# a12008mb.net
KiCad netlist of a schematic drawn in EAGLE
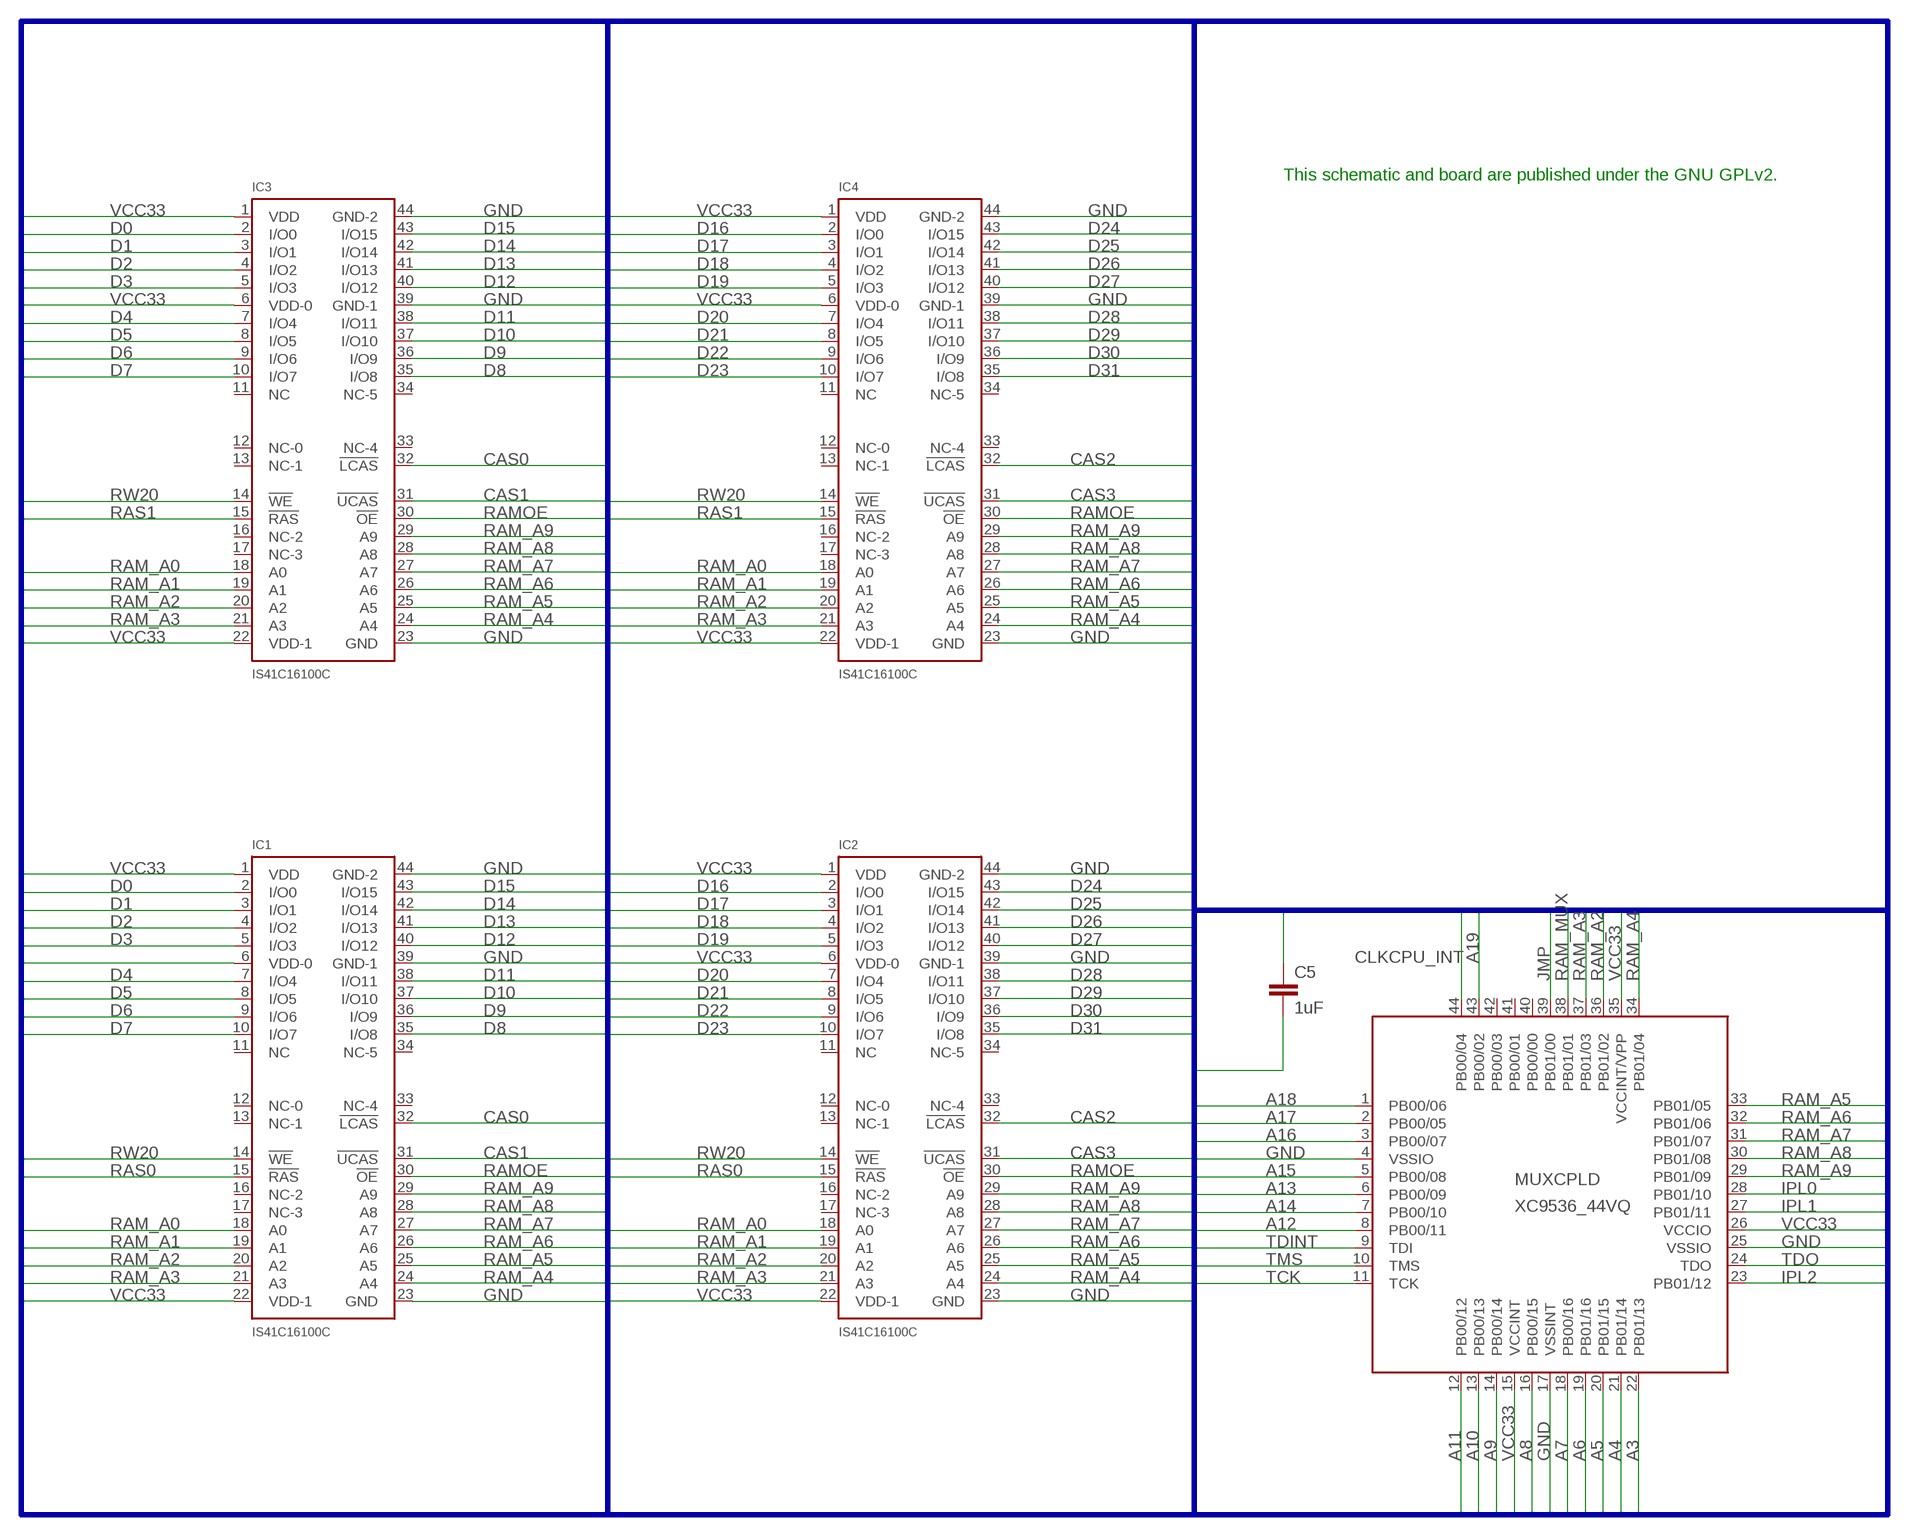
[diagram p0: schematic, sheet 1]
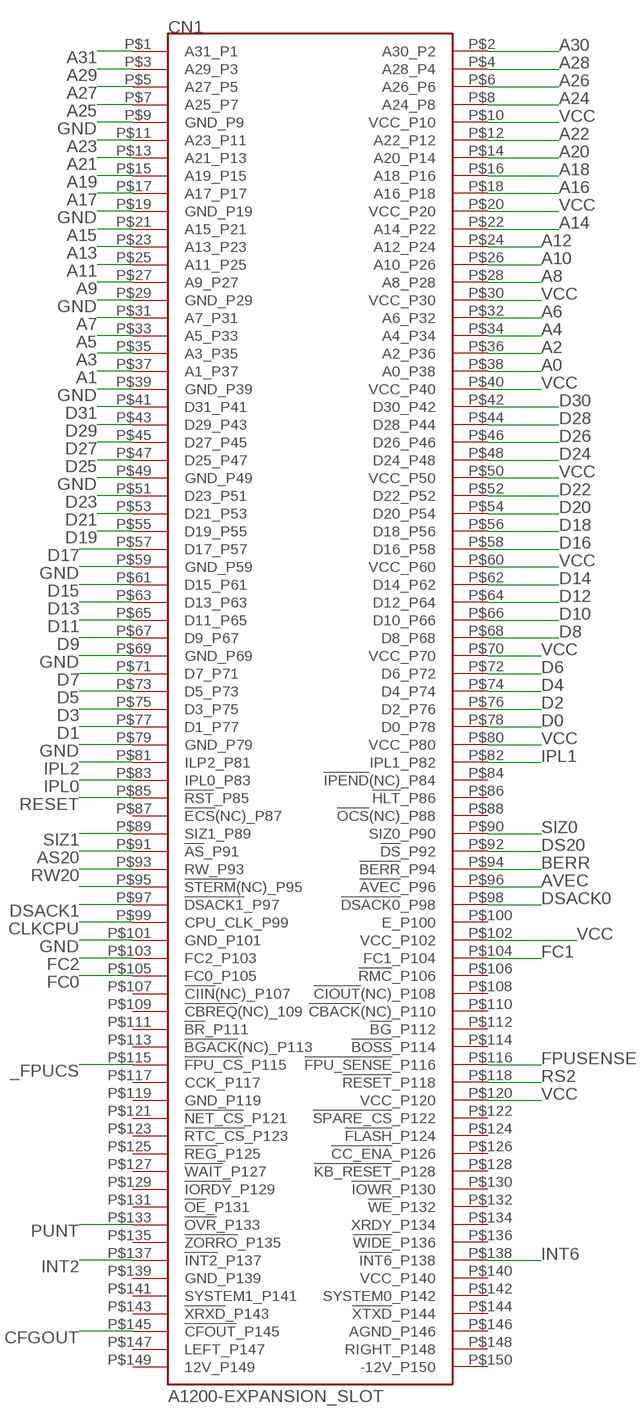
[diagram p1: schematic, sheet 2]
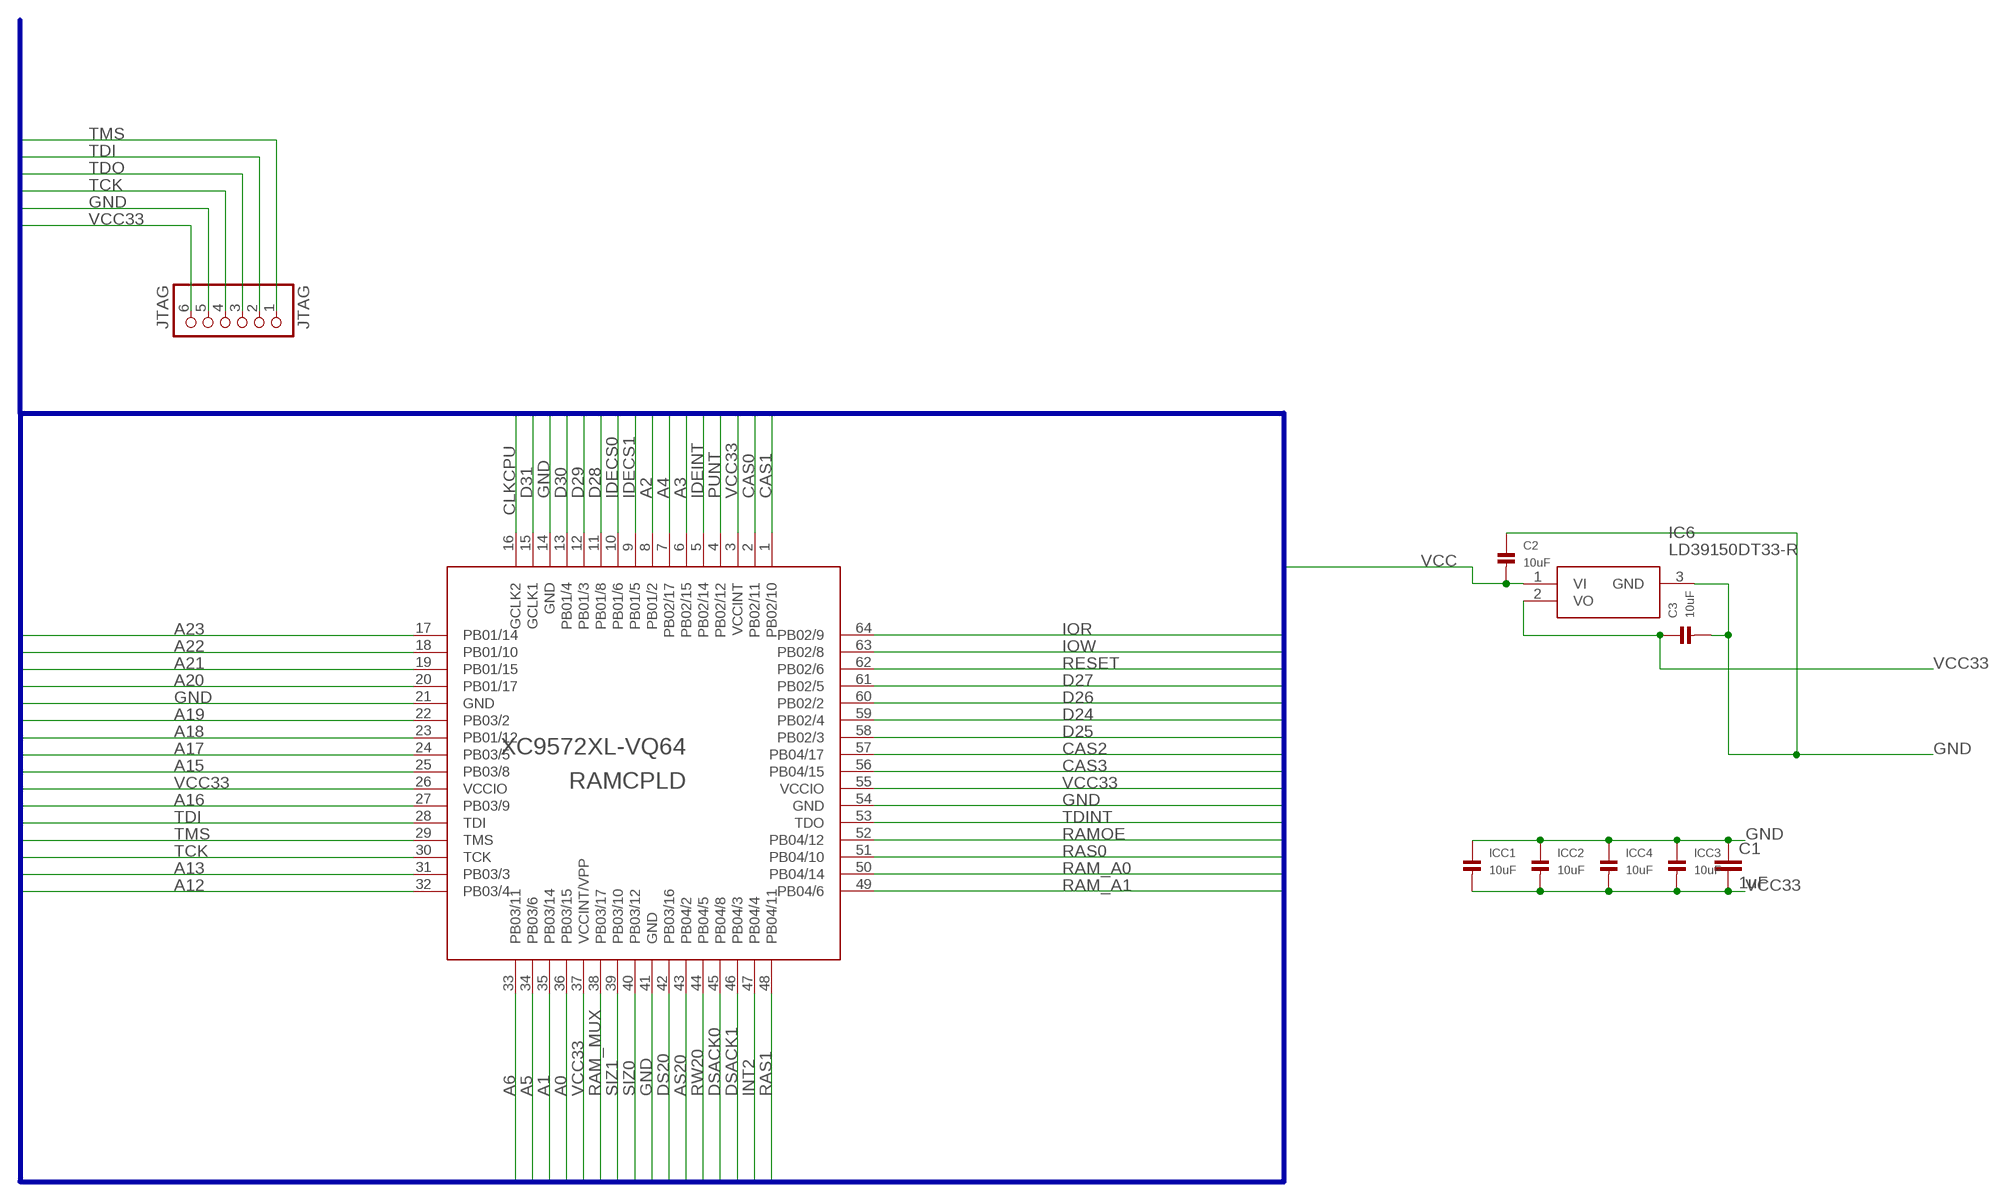
[diagram p2: schematic, sheet 3]

(export (version "E")
  (design (tool "Eeschema 10.0.6"))
  (components
    (comp (ref "C5")
      (value "1uF")
      (footprint "eagle-import:C1206")
      (libsource (lib "eagle-import") (part "CC1206"))
    )
    (comp (ref "IC1")
      (value "IS41C16100C")
      (footprint "eagle-import:TSOP44(50)-II")
      (libsource (lib "eagle-import") (part "IS41C16100C"))
    )
    (comp (ref "IC2")
      (value "IS41C16100C")
      (footprint "eagle-import:TSOP44(50)-II")
      (libsource (lib "eagle-import") (part "IS41C16100C"))
    )
    (comp (ref "IC3")
      (value "IS41C16100C")
      (footprint "eagle-import:TSOP44(50)-II")
      (libsource (lib "eagle-import") (part "IS41C16100C"))
    )
    (comp (ref "IC4")
      (value "IS41C16100C")
      (footprint "eagle-import:TSOP44(50)-II")
      (libsource (lib "eagle-import") (part "IS41C16100C"))
    )
    (comp (ref "MUXCPLD")
      (value "XC9536_44VQ")
      (footprint "eagle-import:SQFP-S-10X10-44")
      (fields (field (name "MPN") "XC9536-15VQG44C"))
      (libsource (lib "eagle-import") (part "XC9536_44VQ"))
    )
    (comp (ref "CN1")
      (value "A1200-EXPANSION_SLOT")
      (footprint "eagle-import:CON_150")
      (libsource (lib "eagle-import") (part "A1200-EXPANSION_SLOT"))
    )
    (comp (ref "C1")
      (value "1uF")
      (footprint "eagle-import:C1206")
      (libsource (lib "eagle-import") (part "CC1206"))
    )
    (comp (ref "C2")
      (value "10uF")
      (footprint "eagle-import:1206")
      (libsource (lib "eagle-import") (part "CAP_CERAMIC1206"))
    )
    (comp (ref "C3")
      (value "10uF")
      (footprint "eagle-import:1206")
      (libsource (lib "eagle-import") (part "CAP_CERAMIC1206"))
    )
    (comp (ref "IC6")
      (value "LD39150DT33-R")
      (footprint "eagle-import:STD5N52U")
      (fields (field (name "MOUSER_PART_NUMBER") "511-LD39150DT33-R"))
      (libsource (lib "eagle-import") (part "LD39150DT33-R"))
    )
    (comp (ref "ICC1")
      (value "10uF")
      (footprint "eagle-import:1206")
      (libsource (lib "eagle-import") (part "CAP_CERAMIC1206"))
    )
    (comp (ref "ICC2")
      (value "10uF")
      (footprint "eagle-import:1206")
      (libsource (lib "eagle-import") (part "CAP_CERAMIC1206"))
    )
    (comp (ref "ICC3")
      (value "10uF")
      (footprint "eagle-import:1206")
      (libsource (lib "eagle-import") (part "CAP_CERAMIC1206"))
    )
    (comp (ref "ICC4")
      (value "10uF")
      (footprint "eagle-import:1206")
      (libsource (lib "eagle-import") (part "CAP_CERAMIC1206"))
    )
    (comp (ref "JTAG")
      (value "JTAG")
      (footprint "eagle-import:1X06_ROUND")
      (libsource (lib "eagle-import") (part "HEADER-1X6ROUND"))
    )
    (comp (ref "RAMCPLD")
      (value "XC9572XL-VQ64")
      (footprint "eagle-import:VQ64")
      (libsource (lib "eagle-import") (part "XC9572XL-VQ64"))
    )
  )
  (nets
    (net (code "1") (name "A0") (class "Default")
      (node (ref "CN1") (pin "P$38") (pinfunction "A0_P38_P$38") (pintype "bidirectional"))
      (node (ref "RAMCPLD") (pin "36") (pinfunction "PB03/15_36") (pintype "bidirectional"))
    )
    (net (code "2") (name "A1") (class "Default")
      (node (ref "CN1") (pin "P$37") (pinfunction "A1_P37_P$37") (pintype "bidirectional"))
      (node (ref "RAMCPLD") (pin "35") (pinfunction "PB03/14_35") (pintype "bidirectional"))
    )
    (net (code "3") (name "A2") (class "Default")
      (node (ref "CN1") (pin "P$36") (pinfunction "A2_P36_P$36") (pintype "bidirectional"))
      (node (ref "RAMCPLD") (pin "8") (pinfunction "PB01/2_8") (pintype "bidirectional"))
    )
    (net (code "4") (name "A3") (class "Default")
      (node (ref "CN1") (pin "P$35") (pinfunction "A3_P35_P$35") (pintype "bidirectional"))
      (node (ref "MUXCPLD") (pin "22") (pinfunction "PB01/13_22") (pintype "bidirectional"))
      (node (ref "RAMCPLD") (pin "6") (pinfunction "PB02/15_6") (pintype "bidirectional"))
    )
    (net (code "5") (name "A4") (class "Default")
      (node (ref "CN1") (pin "P$34") (pinfunction "A4_P34_P$34") (pintype "bidirectional"))
      (node (ref "MUXCPLD") (pin "21") (pinfunction "PB01/14_21") (pintype "bidirectional"))
      (node (ref "RAMCPLD") (pin "7") (pinfunction "PB02/17_7") (pintype "bidirectional"))
    )
    (net (code "6") (name "A5") (class "Default")
      (node (ref "CN1") (pin "P$33") (pinfunction "A5_P33_P$33") (pintype "bidirectional"))
      (node (ref "MUXCPLD") (pin "20") (pinfunction "PB01/15_20") (pintype "bidirectional"))
      (node (ref "RAMCPLD") (pin "34") (pinfunction "PB03/6_34") (pintype "bidirectional"))
    )
    (net (code "7") (name "A6") (class "Default")
      (node (ref "CN1") (pin "P$32") (pinfunction "A6_P32_P$32") (pintype "bidirectional"))
      (node (ref "MUXCPLD") (pin "19") (pinfunction "PB01/16_19") (pintype "bidirectional"))
      (node (ref "RAMCPLD") (pin "33") (pinfunction "PB03/11_33") (pintype "bidirectional"))
    )
    (net (code "8") (name "A7") (class "Default")
      (node (ref "CN1") (pin "P$31") (pinfunction "A7_P31_P$31") (pintype "bidirectional"))
      (node (ref "MUXCPLD") (pin "18") (pinfunction "PB00/16_18") (pintype "bidirectional"))
    )
    (net (code "9") (name "A8") (class "Default")
      (node (ref "CN1") (pin "P$28") (pinfunction "A8_P28_P$28") (pintype "bidirectional"))
      (node (ref "MUXCPLD") (pin "16") (pinfunction "PB00/15_16") (pintype "bidirectional"))
    )
    (net (code "10") (name "A9") (class "Default")
      (node (ref "CN1") (pin "P$27") (pinfunction "A9_P27_P$27") (pintype "bidirectional"))
      (node (ref "MUXCPLD") (pin "14") (pinfunction "PB00/14_14") (pintype "bidirectional"))
    )
    (net (code "11") (name "A10") (class "Default")
      (node (ref "CN1") (pin "P$26") (pinfunction "A10_P26_P$26") (pintype "bidirectional"))
      (node (ref "MUXCPLD") (pin "13") (pinfunction "PB00/13_13") (pintype "bidirectional"))
    )
    (net (code "12") (name "A11") (class "Default")
      (node (ref "CN1") (pin "P$25") (pinfunction "A11_P25_P$25") (pintype "bidirectional"))
      (node (ref "MUXCPLD") (pin "12") (pinfunction "PB00/12_12") (pintype "bidirectional"))
    )
    (net (code "13") (name "A12") (class "Default")
      (node (ref "CN1") (pin "P$24") (pinfunction "A12_P24_P$24") (pintype "bidirectional"))
      (node (ref "MUXCPLD") (pin "8") (pinfunction "PB00/11_8") (pintype "bidirectional"))
      (node (ref "RAMCPLD") (pin "32") (pinfunction "PB03/4_32") (pintype "bidirectional"))
    )
    (net (code "14") (name "A13") (class "Default")
      (node (ref "CN1") (pin "P$23") (pinfunction "A13_P23_P$23") (pintype "bidirectional"))
      (node (ref "MUXCPLD") (pin "6") (pinfunction "PB00/09_6") (pintype "bidirectional"))
      (node (ref "RAMCPLD") (pin "31") (pinfunction "PB03/3_31") (pintype "bidirectional"))
    )
    (net (code "15") (name "A14") (class "Default")
      (node (ref "CN1") (pin "P$22") (pinfunction "A14_P22_P$22") (pintype "bidirectional"))
      (node (ref "MUXCPLD") (pin "7") (pinfunction "PB00/10_7") (pintype "bidirectional"))
    )
    (net (code "16") (name "A15") (class "Default")
      (node (ref "CN1") (pin "P$21") (pinfunction "A15_P21_P$21") (pintype "bidirectional"))
      (node (ref "MUXCPLD") (pin "5") (pinfunction "PB00/08_5") (pintype "bidirectional"))
      (node (ref "RAMCPLD") (pin "25") (pinfunction "PB03/8_25") (pintype "bidirectional"))
    )
    (net (code "17") (name "A16") (class "Default")
      (node (ref "CN1") (pin "P$18") (pinfunction "A16_P18_P$18") (pintype "bidirectional"))
      (node (ref "MUXCPLD") (pin "3") (pinfunction "PB00/07_3") (pintype "bidirectional"))
      (node (ref "RAMCPLD") (pin "27") (pinfunction "PB03/9_27") (pintype "bidirectional"))
    )
    (net (code "18") (name "A17") (class "Default")
      (node (ref "CN1") (pin "P$17") (pinfunction "A17_P17_P$17") (pintype "bidirectional"))
      (node (ref "MUXCPLD") (pin "2") (pinfunction "PB00/05_2") (pintype "bidirectional"))
      (node (ref "RAMCPLD") (pin "24") (pinfunction "PB03/5_24") (pintype "bidirectional"))
    )
    (net (code "19") (name "A18") (class "Default")
      (node (ref "CN1") (pin "P$16") (pinfunction "A18_P16_P$16") (pintype "bidirectional"))
      (node (ref "MUXCPLD") (pin "1") (pinfunction "PB00/06_1") (pintype "bidirectional"))
      (node (ref "RAMCPLD") (pin "23") (pinfunction "PB01/12_23") (pintype "bidirectional"))
    )
    (net (code "20") (name "A19") (class "Default")
      (node (ref "CN1") (pin "P$15") (pinfunction "A19_P15_P$15") (pintype "bidirectional"))
      (node (ref "MUXCPLD") (pin "43") (pinfunction "PB00/02_43") (pintype "bidirectional"))
      (node (ref "RAMCPLD") (pin "22") (pinfunction "PB03/2_22") (pintype "bidirectional"))
    )
    (net (code "21") (name "A20") (class "Default")
      (node (ref "CN1") (pin "P$14") (pinfunction "A20_P14_P$14") (pintype "bidirectional"))
      (node (ref "RAMCPLD") (pin "20") (pinfunction "PB01/17_20") (pintype "bidirectional"))
    )
    (net (code "22") (name "A21") (class "Default")
      (node (ref "CN1") (pin "P$13") (pinfunction "A21_P13_P$13") (pintype "bidirectional"))
      (node (ref "RAMCPLD") (pin "19") (pinfunction "PB01/15_19") (pintype "bidirectional"))
    )
    (net (code "23") (name "A22") (class "Default")
      (node (ref "CN1") (pin "P$12") (pinfunction "A22_P12_P$12") (pintype "bidirectional"))
      (node (ref "RAMCPLD") (pin "18") (pinfunction "PB01/10_18") (pintype "bidirectional"))
    )
    (net (code "24") (name "A23") (class "Default")
      (node (ref "CN1") (pin "P$11") (pinfunction "A23_P11_P$11") (pintype "bidirectional"))
      (node (ref "RAMCPLD") (pin "17") (pinfunction "PB01/14_17") (pintype "bidirectional"))
    )
    (net (code "25") (name "A24") (class "Default")
      (node (ref "CN1") (pin "P$8") (pinfunction "A24_P8_P$8") (pintype "bidirectional"))
    )
    (net (code "26") (name "A25") (class "Default")
      (node (ref "CN1") (pin "P$7") (pinfunction "A25_P7_P$7") (pintype "bidirectional"))
    )
    (net (code "27") (name "A26") (class "Default")
      (node (ref "CN1") (pin "P$6") (pinfunction "A26_P6_P$6") (pintype "bidirectional"))
    )
    (net (code "28") (name "A27") (class "Default")
      (node (ref "CN1") (pin "P$5") (pinfunction "A27_P5_P$5") (pintype "bidirectional"))
    )
    (net (code "29") (name "A28") (class "Default")
      (node (ref "CN1") (pin "P$4") (pinfunction "A28_P4_P$4") (pintype "bidirectional"))
    )
    (net (code "30") (name "A29") (class "Default")
      (node (ref "CN1") (pin "P$3") (pinfunction "A29_P3_P$3") (pintype "bidirectional"))
    )
    (net (code "31") (name "A30") (class "Default")
      (node (ref "CN1") (pin "P$2") (pinfunction "A30_P2_P$2") (pintype "bidirectional"))
    )
    (net (code "32") (name "A31") (class "Default")
      (node (ref "CN1") (pin "P$1") (pinfunction "A31_P1_P$1") (pintype "bidirectional"))
    )
    (net (code "33") (name "AS20") (class "Default")
      (node (ref "CN1") (pin "P$91") (pinfunction "~{AS}_P91_P$91") (pintype "bidirectional"))
      (node (ref "RAMCPLD") (pin "43") (pinfunction "PB04/2_43") (pintype "bidirectional"))
    )
    (net (code "34") (name "AVEC") (class "Default")
      (node (ref "CN1") (pin "P$96") (pinfunction "~{AVEC}_P96_P$96") (pintype "bidirectional"))
    )
    (net (code "35") (name "BERR") (class "Default")
      (node (ref "CN1") (pin "P$94") (pinfunction "~{BERR}_P94_P$94") (pintype "bidirectional"))
    )
    (net (code "36") (name "CAS0") (class "Default")
      (node (ref "IC1") (pin "32") (pinfunction "~{LCAS}_32") (pintype "bidirectional"))
      (node (ref "IC3") (pin "32") (pinfunction "~{LCAS}_32") (pintype "bidirectional"))
      (node (ref "RAMCPLD") (pin "2") (pinfunction "PB02/11_2") (pintype "bidirectional"))
    )
    (net (code "37") (name "CAS1") (class "Default")
      (node (ref "IC1") (pin "31") (pinfunction "~{UCAS}_31") (pintype "bidirectional"))
      (node (ref "IC3") (pin "31") (pinfunction "~{UCAS}_31") (pintype "bidirectional"))
      (node (ref "RAMCPLD") (pin "1") (pinfunction "PB02/10_1") (pintype "bidirectional"))
    )
    (net (code "38") (name "CAS2") (class "Default")
      (node (ref "IC2") (pin "32") (pinfunction "~{LCAS}_32") (pintype "bidirectional"))
      (node (ref "IC4") (pin "32") (pinfunction "~{LCAS}_32") (pintype "bidirectional"))
      (node (ref "RAMCPLD") (pin "57") (pinfunction "PB04/17_57") (pintype "bidirectional"))
    )
    (net (code "39") (name "CAS3") (class "Default")
      (node (ref "IC2") (pin "31") (pinfunction "~{UCAS}_31") (pintype "bidirectional"))
      (node (ref "IC4") (pin "31") (pinfunction "~{UCAS}_31") (pintype "bidirectional"))
      (node (ref "RAMCPLD") (pin "56") (pinfunction "PB04/15_56") (pintype "bidirectional"))
    )
    (net (code "40") (name "CFGOUT") (class "Default")
      (node (ref "CN1") (pin "P$145") (pinfunction "~{CFOUT}_P145_P$145") (pintype "bidirectional"))
    )
    (net (code "41") (name "CLKCPU") (class "Default")
      (node (ref "CN1") (pin "P$99") (pinfunction "CPU_CLK_P99_P$99") (pintype "bidirectional"))
      (node (ref "RAMCPLD") (pin "16") (pinfunction "GCLK2_16") (pintype "bidirectional"))
    )
    (net (code "42") (name "CLKCPU_INT") (class "Default")
      (node (ref "MUXCPLD") (pin "44") (pinfunction "PB00/04_44") (pintype "bidirectional"))
    )
    (net (code "43") (name "D0") (class "Default")
      (node (ref "CN1") (pin "P$78") (pinfunction "D0_P78_P$78") (pintype "bidirectional"))
      (node (ref "IC1") (pin "2") (pinfunction "I/O0_2") (pintype "bidirectional"))
      (node (ref "IC3") (pin "2") (pinfunction "I/O0_2") (pintype "bidirectional"))
    )
    (net (code "44") (name "D1") (class "Default")
      (node (ref "CN1") (pin "P$77") (pinfunction "D1_P77_P$77") (pintype "bidirectional"))
      (node (ref "IC1") (pin "3") (pinfunction "I/O1_3") (pintype "bidirectional"))
      (node (ref "IC3") (pin "3") (pinfunction "I/O1_3") (pintype "bidirectional"))
    )
    (net (code "45") (name "D2") (class "Default")
      (node (ref "CN1") (pin "P$76") (pinfunction "D2_P76_P$76") (pintype "bidirectional"))
      (node (ref "IC1") (pin "4") (pinfunction "I/O2_4") (pintype "bidirectional"))
      (node (ref "IC3") (pin "4") (pinfunction "I/O2_4") (pintype "bidirectional"))
    )
    (net (code "46") (name "D3") (class "Default")
      (node (ref "CN1") (pin "P$75") (pinfunction "D3_P75_P$75") (pintype "bidirectional"))
      (node (ref "IC1") (pin "5") (pinfunction "I/O3_5") (pintype "bidirectional"))
      (node (ref "IC3") (pin "5") (pinfunction "I/O3_5") (pintype "bidirectional"))
    )
    (net (code "47") (name "D4") (class "Default")
      (node (ref "CN1") (pin "P$74") (pinfunction "D4_P74_P$74") (pintype "bidirectional"))
      (node (ref "IC1") (pin "7") (pinfunction "I/O4_7") (pintype "bidirectional"))
      (node (ref "IC3") (pin "7") (pinfunction "I/O4_7") (pintype "bidirectional"))
    )
    (net (code "48") (name "D5") (class "Default")
      (node (ref "CN1") (pin "P$73") (pinfunction "D5_P73_P$73") (pintype "bidirectional"))
      (node (ref "IC1") (pin "8") (pinfunction "I/O5_8") (pintype "bidirectional"))
      (node (ref "IC3") (pin "8") (pinfunction "I/O5_8") (pintype "bidirectional"))
    )
    (net (code "49") (name "D6") (class "Default")
      (node (ref "CN1") (pin "P$72") (pinfunction "D6_P72_P$72") (pintype "bidirectional"))
      (node (ref "IC1") (pin "9") (pinfunction "I/O6_9") (pintype "bidirectional"))
      (node (ref "IC3") (pin "9") (pinfunction "I/O6_9") (pintype "bidirectional"))
    )
    (net (code "50") (name "D7") (class "Default")
      (node (ref "CN1") (pin "P$71") (pinfunction "D7_P71_P$71") (pintype "bidirectional"))
      (node (ref "IC1") (pin "10") (pinfunction "I/O7_10") (pintype "bidirectional"))
      (node (ref "IC3") (pin "10") (pinfunction "I/O7_10") (pintype "bidirectional"))
    )
    (net (code "51") (name "D8") (class "Default")
      (node (ref "CN1") (pin "P$68") (pinfunction "D8_P68_P$68") (pintype "bidirectional"))
      (node (ref "IC1") (pin "35") (pinfunction "I/O8_35") (pintype "bidirectional"))
      (node (ref "IC3") (pin "35") (pinfunction "I/O8_35") (pintype "bidirectional"))
    )
    (net (code "52") (name "D9") (class "Default")
      (node (ref "CN1") (pin "P$67") (pinfunction "D9_P67_P$67") (pintype "bidirectional"))
      (node (ref "IC1") (pin "36") (pinfunction "I/O9_36") (pintype "bidirectional"))
      (node (ref "IC3") (pin "36") (pinfunction "I/O9_36") (pintype "bidirectional"))
    )
    (net (code "53") (name "D10") (class "Default")
      (node (ref "CN1") (pin "P$66") (pinfunction "D10_P66_P$66") (pintype "bidirectional"))
      (node (ref "IC1") (pin "37") (pinfunction "I/O10_37") (pintype "bidirectional"))
      (node (ref "IC3") (pin "37") (pinfunction "I/O10_37") (pintype "bidirectional"))
    )
    (net (code "54") (name "D11") (class "Default")
      (node (ref "CN1") (pin "P$65") (pinfunction "D11_P65_P$65") (pintype "bidirectional"))
      (node (ref "IC1") (pin "38") (pinfunction "I/O11_38") (pintype "bidirectional"))
      (node (ref "IC3") (pin "38") (pinfunction "I/O11_38") (pintype "bidirectional"))
    )
    (net (code "55") (name "D12") (class "Default")
      (node (ref "CN1") (pin "P$64") (pinfunction "D12_P64_P$64") (pintype "bidirectional"))
      (node (ref "IC1") (pin "40") (pinfunction "I/O12_40") (pintype "bidirectional"))
      (node (ref "IC3") (pin "40") (pinfunction "I/O12_40") (pintype "bidirectional"))
    )
    (net (code "56") (name "D13") (class "Default")
      (node (ref "CN1") (pin "P$63") (pinfunction "D13_P63_P$63") (pintype "bidirectional"))
      (node (ref "IC1") (pin "41") (pinfunction "I/O13_41") (pintype "bidirectional"))
      (node (ref "IC3") (pin "41") (pinfunction "I/O13_41") (pintype "bidirectional"))
    )
    (net (code "57") (name "D14") (class "Default")
      (node (ref "CN1") (pin "P$62") (pinfunction "D14_P62_P$62") (pintype "bidirectional"))
      (node (ref "IC1") (pin "42") (pinfunction "I/O14_42") (pintype "bidirectional"))
      (node (ref "IC3") (pin "42") (pinfunction "I/O14_42") (pintype "bidirectional"))
    )
    (net (code "58") (name "D15") (class "Default")
      (node (ref "CN1") (pin "P$61") (pinfunction "D15_P61_P$61") (pintype "bidirectional"))
      (node (ref "IC1") (pin "43") (pinfunction "I/O15_43") (pintype "bidirectional"))
      (node (ref "IC3") (pin "43") (pinfunction "I/O15_43") (pintype "bidirectional"))
    )
    (net (code "59") (name "D16") (class "Default")
      (node (ref "CN1") (pin "P$58") (pinfunction "D16_P58_P$58") (pintype "bidirectional"))
      (node (ref "IC2") (pin "2") (pinfunction "I/O0_2") (pintype "bidirectional"))
      (node (ref "IC4") (pin "2") (pinfunction "I/O0_2") (pintype "bidirectional"))
    )
    (net (code "60") (name "D17") (class "Default")
      (node (ref "CN1") (pin "P$57") (pinfunction "D17_P57_P$57") (pintype "bidirectional"))
      (node (ref "IC2") (pin "3") (pinfunction "I/O1_3") (pintype "bidirectional"))
      (node (ref "IC4") (pin "3") (pinfunction "I/O1_3") (pintype "bidirectional"))
    )
    (net (code "61") (name "D18") (class "Default")
      (node (ref "CN1") (pin "P$56") (pinfunction "D18_P56_P$56") (pintype "bidirectional"))
      (node (ref "IC2") (pin "4") (pinfunction "I/O2_4") (pintype "bidirectional"))
      (node (ref "IC4") (pin "4") (pinfunction "I/O2_4") (pintype "bidirectional"))
    )
    (net (code "62") (name "D19") (class "Default")
      (node (ref "CN1") (pin "P$55") (pinfunction "D19_P55_P$55") (pintype "bidirectional"))
      (node (ref "IC2") (pin "5") (pinfunction "I/O3_5") (pintype "bidirectional"))
      (node (ref "IC4") (pin "5") (pinfunction "I/O3_5") (pintype "bidirectional"))
    )
    (net (code "63") (name "D20") (class "Default")
      (node (ref "CN1") (pin "P$54") (pinfunction "D20_P54_P$54") (pintype "bidirectional"))
      (node (ref "IC2") (pin "7") (pinfunction "I/O4_7") (pintype "bidirectional"))
      (node (ref "IC4") (pin "7") (pinfunction "I/O4_7") (pintype "bidirectional"))
    )
    (net (code "64") (name "D21") (class "Default")
      (node (ref "CN1") (pin "P$53") (pinfunction "D21_P53_P$53") (pintype "bidirectional"))
      (node (ref "IC2") (pin "8") (pinfunction "I/O5_8") (pintype "bidirectional"))
      (node (ref "IC4") (pin "8") (pinfunction "I/O5_8") (pintype "bidirectional"))
    )
    (net (code "65") (name "D22") (class "Default")
      (node (ref "CN1") (pin "P$52") (pinfunction "D22_P52_P$52") (pintype "bidirectional"))
      (node (ref "IC2") (pin "9") (pinfunction "I/O6_9") (pintype "bidirectional"))
      (node (ref "IC4") (pin "9") (pinfunction "I/O6_9") (pintype "bidirectional"))
    )
    (net (code "66") (name "D23") (class "Default")
      (node (ref "CN1") (pin "P$51") (pinfunction "D23_P51_P$51") (pintype "bidirectional"))
      (node (ref "IC2") (pin "10") (pinfunction "I/O7_10") (pintype "bidirectional"))
      (node (ref "IC4") (pin "10") (pinfunction "I/O7_10") (pintype "bidirectional"))
    )
    (net (code "67") (name "D24") (class "Default")
      (node (ref "CN1") (pin "P$48") (pinfunction "D24_P48_P$48") (pintype "bidirectional"))
      (node (ref "IC2") (pin "43") (pinfunction "I/O15_43") (pintype "bidirectional"))
      (node (ref "IC4") (pin "43") (pinfunction "I/O15_43") (pintype "bidirectional"))
      (node (ref "RAMCPLD") (pin "59") (pinfunction "PB02/4_59") (pintype "bidirectional"))
    )
    (net (code "68") (name "D25") (class "Default")
      (node (ref "CN1") (pin "P$47") (pinfunction "D25_P47_P$47") (pintype "bidirectional"))
      (node (ref "IC2") (pin "42") (pinfunction "I/O14_42") (pintype "bidirectional"))
      (node (ref "IC4") (pin "42") (pinfunction "I/O14_42") (pintype "bidirectional"))
      (node (ref "RAMCPLD") (pin "58") (pinfunction "PB02/3_58") (pintype "bidirectional"))
    )
    (net (code "69") (name "D26") (class "Default")
      (node (ref "CN1") (pin "P$46") (pinfunction "D26_P46_P$46") (pintype "bidirectional"))
      (node (ref "IC2") (pin "41") (pinfunction "I/O13_41") (pintype "bidirectional"))
      (node (ref "IC4") (pin "41") (pinfunction "I/O13_41") (pintype "bidirectional"))
      (node (ref "RAMCPLD") (pin "60") (pinfunction "PB02/2_60") (pintype "bidirectional"))
    )
    (net (code "70") (name "D27") (class "Default")
      (node (ref "CN1") (pin "P$45") (pinfunction "D27_P45_P$45") (pintype "bidirectional"))
      (node (ref "IC2") (pin "40") (pinfunction "I/O12_40") (pintype "bidirectional"))
      (node (ref "IC4") (pin "40") (pinfunction "I/O12_40") (pintype "bidirectional"))
      (node (ref "RAMCPLD") (pin "61") (pinfunction "PB02/5_61") (pintype "bidirectional"))
    )
    (net (code "71") (name "D28") (class "Default")
      (node (ref "CN1") (pin "P$44") (pinfunction "D28_P44_P$44") (pintype "bidirectional"))
      (node (ref "IC2") (pin "38") (pinfunction "I/O11_38") (pintype "bidirectional"))
      (node (ref "IC4") (pin "38") (pinfunction "I/O11_38") (pintype "bidirectional"))
      (node (ref "RAMCPLD") (pin "11") (pinfunction "PB01/8_11") (pintype "bidirectional"))
    )
    (net (code "72") (name "D29") (class "Default")
      (node (ref "CN1") (pin "P$43") (pinfunction "D29_P43_P$43") (pintype "bidirectional"))
      (node (ref "IC2") (pin "37") (pinfunction "I/O10_37") (pintype "bidirectional"))
      (node (ref "IC4") (pin "37") (pinfunction "I/O10_37") (pintype "bidirectional"))
      (node (ref "RAMCPLD") (pin "12") (pinfunction "PB01/3_12") (pintype "bidirectional"))
    )
    (net (code "73") (name "D30") (class "Default")
      (node (ref "CN1") (pin "P$42") (pinfunction "D30_P42_P$42") (pintype "bidirectional"))
      (node (ref "IC2") (pin "36") (pinfunction "I/O9_36") (pintype "bidirectional"))
      (node (ref "IC4") (pin "36") (pinfunction "I/O9_36") (pintype "bidirectional"))
      (node (ref "RAMCPLD") (pin "13") (pinfunction "PB01/4_13") (pintype "bidirectional"))
    )
    (net (code "74") (name "D31") (class "Default")
      (node (ref "CN1") (pin "P$41") (pinfunction "D31_P41_P$41") (pintype "bidirectional"))
      (node (ref "IC2") (pin "35") (pinfunction "I/O8_35") (pintype "bidirectional"))
      (node (ref "IC4") (pin "35") (pinfunction "I/O8_35") (pintype "bidirectional"))
      (node (ref "RAMCPLD") (pin "15") (pinfunction "GCLK1_15") (pintype "bidirectional"))
    )
    (net (code "75") (name "DS20") (class "Default")
      (node (ref "CN1") (pin "P$92") (pinfunction "~{DS}_P92_P$92") (pintype "bidirectional"))
      (node (ref "RAMCPLD") (pin "42") (pinfunction "PB03/16_42") (pintype "bidirectional"))
    )
    (net (code "76") (name "DSACK0") (class "Default")
      (node (ref "CN1") (pin "P$98") (pinfunction "~{DSACK0}_P98_P$98") (pintype "bidirectional"))
      (node (ref "RAMCPLD") (pin "45") (pinfunction "PB04/8_45") (pintype "bidirectional"))
    )
    (net (code "77") (name "DSACK1") (class "Default")
      (node (ref "CN1") (pin "P$97") (pinfunction "~{DSACK1}_P97_P$97") (pintype "bidirectional"))
      (node (ref "RAMCPLD") (pin "46") (pinfunction "PB04/3_46") (pintype "bidirectional"))
    )
    (net (code "78") (name "FC0") (class "Default")
      (node (ref "CN1") (pin "P$105") (pinfunction "FC0_P105_P$105") (pintype "bidirectional"))
    )
    (net (code "79") (name "FC1") (class "Default")
      (node (ref "CN1") (pin "P$104") (pinfunction "FC1_P104_P$104") (pintype "bidirectional"))
    )
    (net (code "80") (name "FC2") (class "Default")
      (node (ref "CN1") (pin "P$103") (pinfunction "FC2_P103_P$103") (pintype "bidirectional"))
    )
    (net (code "81") (name "FPUSENSE") (class "Default")
      (node (ref "CN1") (pin "P$116") (pinfunction "~{FPU_SENSE}_P116_P$116") (pintype "bidirectional"))
    )
    (net (code "82") (name "GND") (class "Default")
      (node (ref "C1") (pin "1") (pinfunction "1_1") (pintype "passive"))
      (node (ref "C2") (pin "1") (pinfunction "P$1_1") (pintype "passive"))
      (node (ref "C3") (pin "2") (pinfunction "P$2_2") (pintype "passive"))
      (node (ref "C5") (pin "2") (pinfunction "2_2") (pintype "passive"))
      (node (ref "CN1") (pin "P$101") (pinfunction "GND_P101_P$101") (pintype "bidirectional"))
      (node (ref "CN1") (pin "P$19") (pinfunction "GND_P19_P$19") (pintype "bidirectional"))
      (node (ref "CN1") (pin "P$29") (pinfunction "GND_P29_P$29") (pintype "bidirectional"))
      (node (ref "CN1") (pin "P$39") (pinfunction "GND_P39_P$39") (pintype "bidirectional"))
      (node (ref "CN1") (pin "P$49") (pinfunction "GND_P49_P$49") (pintype "bidirectional"))
      (node (ref "CN1") (pin "P$59") (pinfunction "GND_P59_P$59") (pintype "bidirectional"))
      (node (ref "CN1") (pin "P$69") (pinfunction "GND_P69_P$69") (pintype "bidirectional"))
      (node (ref "CN1") (pin "P$79") (pinfunction "GND_P79_P$79") (pintype "bidirectional"))
      (node (ref "CN1") (pin "P$9") (pinfunction "GND_P9_P$9") (pintype "bidirectional"))
      (node (ref "IC1") (pin "23") (pinfunction "GND_23") (pintype "bidirectional"))
      (node (ref "IC1") (pin "39") (pinfunction "GND-1_39") (pintype "bidirectional"))
      (node (ref "IC1") (pin "44") (pinfunction "GND-2_44") (pintype "bidirectional"))
      (node (ref "IC2") (pin "23") (pinfunction "GND_23") (pintype "bidirectional"))
      (node (ref "IC2") (pin "39") (pinfunction "GND-1_39") (pintype "bidirectional"))
      (node (ref "IC2") (pin "44") (pinfunction "GND-2_44") (pintype "bidirectional"))
      (node (ref "IC3") (pin "23") (pinfunction "GND_23") (pintype "bidirectional"))
      (node (ref "IC3") (pin "39") (pinfunction "GND-1_39") (pintype "bidirectional"))
      (node (ref "IC3") (pin "44") (pinfunction "GND-2_44") (pintype "bidirectional"))
      (node (ref "IC4") (pin "23") (pinfunction "GND_23") (pintype "bidirectional"))
      (node (ref "IC4") (pin "39") (pinfunction "GND-1_39") (pintype "bidirectional"))
      (node (ref "IC4") (pin "44") (pinfunction "GND-2_44") (pintype "bidirectional"))
      (node (ref "IC6") (pin "3") (pinfunction "GND_3") (pintype "bidirectional"))
      (node (ref "ICC1") (pin "1") (pinfunction "P$1_1") (pintype "passive"))
      (node (ref "ICC2") (pin "1") (pinfunction "P$1_1") (pintype "passive"))
      (node (ref "ICC3") (pin "1") (pinfunction "P$1_1") (pintype "passive"))
      (node (ref "ICC4") (pin "1") (pinfunction "P$1_1") (pintype "passive"))
      (node (ref "JTAG") (pin "5") (pinfunction "5_5") (pintype "passive"))
      (node (ref "MUXCPLD") (pin "17") (pinfunction "VSSINT_17") (pintype "power_in"))
      (node (ref "MUXCPLD") (pin "25") (pinfunction "VSSIO_25") (pintype "power_in"))
      (node (ref "MUXCPLD") (pin "4") (pinfunction "VSSIO_4") (pintype "power_in"))
      (node (ref "RAMCPLD") (pin "14") (pinfunction "GND_14") (pintype "bidirectional"))
      (node (ref "RAMCPLD") (pin "21") (pinfunction "GND_21") (pintype "bidirectional"))
      (node (ref "RAMCPLD") (pin "41") (pinfunction "GND_41") (pintype "bidirectional"))
      (node (ref "RAMCPLD") (pin "54") (pinfunction "GND_54") (pintype "bidirectional"))
    )
    (net (code "83") (name "IDECS0") (class "Default")
      (node (ref "RAMCPLD") (pin "10") (pinfunction "PB01/6_10") (pintype "bidirectional"))
    )
    (net (code "84") (name "IDECS1") (class "Default")
      (node (ref "RAMCPLD") (pin "9") (pinfunction "PB01/5_9") (pintype "bidirectional"))
    )
    (net (code "85") (name "IDEINT") (class "Default")
      (node (ref "RAMCPLD") (pin "5") (pinfunction "PB02/14_5") (pintype "bidirectional"))
    )
    (net (code "86") (name "INT2") (class "Default")
      (node (ref "CN1") (pin "P$137") (pinfunction "~{INT2}_P137_P$137") (pintype "bidirectional"))
      (node (ref "RAMCPLD") (pin "47") (pinfunction "PB04/4_47") (pintype "bidirectional"))
    )
    (net (code "87") (name "INT6") (class "Default")
      (node (ref "CN1") (pin "P$138") (pinfunction "~{INT6}_P138_P$138") (pintype "bidirectional"))
    )
    (net (code "88") (name "IOR") (class "Default")
      (node (ref "RAMCPLD") (pin "64") (pinfunction "PB02/9_64") (pintype "bidirectional"))
    )
    (net (code "89") (name "IOW") (class "Default")
      (node (ref "RAMCPLD") (pin "63") (pinfunction "PB02/8_63") (pintype "bidirectional"))
    )
    (net (code "90") (name "IPL0") (class "Default")
      (node (ref "CN1") (pin "P$83") (pinfunction "IPL0_P83_P$83") (pintype "bidirectional"))
      (node (ref "MUXCPLD") (pin "28") (pinfunction "PB01/10_28") (pintype "bidirectional"))
    )
    (net (code "91") (name "IPL1") (class "Default")
      (node (ref "CN1") (pin "P$82") (pinfunction "IPL1_P82_P$82") (pintype "bidirectional"))
      (node (ref "MUXCPLD") (pin "27") (pinfunction "PB01/11_27") (pintype "bidirectional"))
    )
    (net (code "92") (name "IPL2") (class "Default")
      (node (ref "CN1") (pin "P$81") (pinfunction "ILP2_P81_P$81") (pintype "bidirectional"))
      (node (ref "MUXCPLD") (pin "23") (pinfunction "PB01/12_23") (pintype "bidirectional"))
    )
    (net (code "93") (name "JMP") (class "Default")
      (node (ref "MUXCPLD") (pin "39") (pinfunction "PB01/00_39") (pintype "bidirectional"))
    )
    (net (code "94") (name "PUNT") (class "Default")
      (node (ref "CN1") (pin "P$133") (pinfunction "~{OVR}_P133_P$133") (pintype "bidirectional"))
      (node (ref "RAMCPLD") (pin "4") (pinfunction "PB02/12_4") (pintype "bidirectional"))
    )
    (net (code "95") (name "RAMOE") (class "Default")
      (node (ref "IC1") (pin "30") (pinfunction "~{OE}_30") (pintype "bidirectional"))
      (node (ref "IC2") (pin "30") (pinfunction "~{OE}_30") (pintype "bidirectional"))
      (node (ref "IC3") (pin "30") (pinfunction "~{OE}_30") (pintype "bidirectional"))
      (node (ref "IC4") (pin "30") (pinfunction "~{OE}_30") (pintype "bidirectional"))
      (node (ref "RAMCPLD") (pin "52") (pinfunction "PB04/12_52") (pintype "bidirectional"))
    )
    (net (code "96") (name "RAM_A0") (class "Default")
      (node (ref "IC1") (pin "18") (pinfunction "A0_18") (pintype "bidirectional"))
      (node (ref "IC2") (pin "18") (pinfunction "A0_18") (pintype "bidirectional"))
      (node (ref "IC3") (pin "18") (pinfunction "A0_18") (pintype "bidirectional"))
      (node (ref "IC4") (pin "18") (pinfunction "A0_18") (pintype "bidirectional"))
      (node (ref "RAMCPLD") (pin "50") (pinfunction "PB04/14_50") (pintype "bidirectional"))
    )
    (net (code "97") (name "RAM_A1") (class "Default")
      (node (ref "IC1") (pin "19") (pinfunction "A1_19") (pintype "bidirectional"))
      (node (ref "IC2") (pin "19") (pinfunction "A1_19") (pintype "bidirectional"))
      (node (ref "IC3") (pin "19") (pinfunction "A1_19") (pintype "bidirectional"))
      (node (ref "IC4") (pin "19") (pinfunction "A1_19") (pintype "bidirectional"))
      (node (ref "RAMCPLD") (pin "49") (pinfunction "PB04/6_49") (pintype "bidirectional"))
    )
    (net (code "98") (name "RAM_A2") (class "Default")
      (node (ref "IC1") (pin "20") (pinfunction "A2_20") (pintype "bidirectional"))
      (node (ref "IC2") (pin "20") (pinfunction "A2_20") (pintype "bidirectional"))
      (node (ref "IC3") (pin "20") (pinfunction "A2_20") (pintype "bidirectional"))
      (node (ref "IC4") (pin "20") (pinfunction "A2_20") (pintype "bidirectional"))
      (node (ref "MUXCPLD") (pin "36") (pinfunction "PB01/02_36") (pintype "bidirectional"))
    )
    (net (code "99") (name "RAM_A3") (class "Default")
      (node (ref "IC1") (pin "21") (pinfunction "A3_21") (pintype "bidirectional"))
      (node (ref "IC2") (pin "21") (pinfunction "A3_21") (pintype "bidirectional"))
      (node (ref "IC3") (pin "21") (pinfunction "A3_21") (pintype "bidirectional"))
      (node (ref "IC4") (pin "21") (pinfunction "A3_21") (pintype "bidirectional"))
      (node (ref "MUXCPLD") (pin "37") (pinfunction "PB01/03_37") (pintype "bidirectional"))
    )
    (net (code "100") (name "RAM_A4") (class "Default")
      (node (ref "IC1") (pin "24") (pinfunction "A4_24") (pintype "bidirectional"))
      (node (ref "IC2") (pin "24") (pinfunction "A4_24") (pintype "bidirectional"))
      (node (ref "IC3") (pin "24") (pinfunction "A4_24") (pintype "bidirectional"))
      (node (ref "IC4") (pin "24") (pinfunction "A4_24") (pintype "bidirectional"))
      (node (ref "MUXCPLD") (pin "34") (pinfunction "PB01/04_34") (pintype "bidirectional"))
    )
    (net (code "101") (name "RAM_A5") (class "Default")
      (node (ref "IC1") (pin "25") (pinfunction "A5_25") (pintype "bidirectional"))
      (node (ref "IC2") (pin "25") (pinfunction "A5_25") (pintype "bidirectional"))
      (node (ref "IC3") (pin "25") (pinfunction "A5_25") (pintype "bidirectional"))
      (node (ref "IC4") (pin "25") (pinfunction "A5_25") (pintype "bidirectional"))
      (node (ref "MUXCPLD") (pin "33") (pinfunction "PB01/05_33") (pintype "bidirectional"))
    )
    (net (code "102") (name "RAM_A6") (class "Default")
      (node (ref "IC1") (pin "26") (pinfunction "A6_26") (pintype "bidirectional"))
      (node (ref "IC2") (pin "26") (pinfunction "A6_26") (pintype "bidirectional"))
      (node (ref "IC3") (pin "26") (pinfunction "A6_26") (pintype "bidirectional"))
      (node (ref "IC4") (pin "26") (pinfunction "A6_26") (pintype "bidirectional"))
      (node (ref "MUXCPLD") (pin "32") (pinfunction "PB01/06_32") (pintype "bidirectional"))
    )
    (net (code "103") (name "RAM_A7") (class "Default")
      (node (ref "IC1") (pin "27") (pinfunction "A7_27") (pintype "bidirectional"))
      (node (ref "IC2") (pin "27") (pinfunction "A7_27") (pintype "bidirectional"))
      (node (ref "IC3") (pin "27") (pinfunction "A7_27") (pintype "bidirectional"))
      (node (ref "IC4") (pin "27") (pinfunction "A7_27") (pintype "bidirectional"))
      (node (ref "MUXCPLD") (pin "31") (pinfunction "PB01/07_31") (pintype "bidirectional"))
    )
    (net (code "104") (name "RAM_A8") (class "Default")
      (node (ref "IC1") (pin "28") (pinfunction "A8_28") (pintype "bidirectional"))
      (node (ref "IC2") (pin "28") (pinfunction "A8_28") (pintype "bidirectional"))
      (node (ref "IC3") (pin "28") (pinfunction "A8_28") (pintype "bidirectional"))
      (node (ref "IC4") (pin "28") (pinfunction "A8_28") (pintype "bidirectional"))
      (node (ref "MUXCPLD") (pin "30") (pinfunction "PB01/08_30") (pintype "bidirectional"))
    )
    (net (code "105") (name "RAM_A9") (class "Default")
      (node (ref "IC1") (pin "29") (pinfunction "A9_29") (pintype "bidirectional"))
      (node (ref "IC2") (pin "29") (pinfunction "A9_29") (pintype "bidirectional"))
      (node (ref "IC3") (pin "29") (pinfunction "A9_29") (pintype "bidirectional"))
      (node (ref "IC4") (pin "29") (pinfunction "A9_29") (pintype "bidirectional"))
      (node (ref "MUXCPLD") (pin "29") (pinfunction "PB01/09_29") (pintype "bidirectional"))
    )
    (net (code "106") (name "RAM_MUX") (class "Default")
      (node (ref "MUXCPLD") (pin "38") (pinfunction "PB01/01_38") (pintype "bidirectional"))
      (node (ref "RAMCPLD") (pin "38") (pinfunction "PB03/17_38") (pintype "bidirectional"))
    )
    (net (code "107") (name "RAS0") (class "Default")
      (node (ref "IC1") (pin "15") (pinfunction "~{RAS}_15") (pintype "bidirectional"))
      (node (ref "IC2") (pin "15") (pinfunction "~{RAS}_15") (pintype "bidirectional"))
      (node (ref "RAMCPLD") (pin "51") (pinfunction "PB04/10_51") (pintype "bidirectional"))
    )
    (net (code "108") (name "RAS1") (class "Default")
      (node (ref "IC3") (pin "15") (pinfunction "~{RAS}_15") (pintype "bidirectional"))
      (node (ref "IC4") (pin "15") (pinfunction "~{RAS}_15") (pintype "bidirectional"))
      (node (ref "RAMCPLD") (pin "48") (pinfunction "PB04/11_48") (pintype "bidirectional"))
    )
    (net (code "109") (name "RESET") (class "Default")
      (node (ref "CN1") (pin "P$85") (pinfunction "~{RST}_P85_P$85") (pintype "bidirectional"))
      (node (ref "RAMCPLD") (pin "62") (pinfunction "PB02/6_62") (pintype "bidirectional"))
    )
    (net (code "110") (name "RS2") (class "Default")
      (node (ref "CN1") (pin "P$118") (pinfunction "~{RESET}_P118_P$118") (pintype "bidirectional"))
    )
    (net (code "111") (name "RW20") (class "Default")
      (node (ref "CN1") (pin "P$93") (pinfunction "RW_P93_P$93") (pintype "bidirectional"))
      (node (ref "IC1") (pin "14") (pinfunction "~{WE}_14") (pintype "bidirectional"))
      (node (ref "IC2") (pin "14") (pinfunction "~{WE}_14") (pintype "bidirectional"))
      (node (ref "IC3") (pin "14") (pinfunction "~{WE}_14") (pintype "bidirectional"))
      (node (ref "IC4") (pin "14") (pinfunction "~{WE}_14") (pintype "bidirectional"))
      (node (ref "RAMCPLD") (pin "44") (pinfunction "PB04/5_44") (pintype "bidirectional"))
    )
    (net (code "112") (name "SIZ0") (class "Default")
      (node (ref "CN1") (pin "P$90") (pinfunction "SIZ0_P90_P$90") (pintype "bidirectional"))
      (node (ref "RAMCPLD") (pin "40") (pinfunction "PB03/12_40") (pintype "bidirectional"))
    )
    (net (code "113") (name "SIZ1") (class "Default")
      (node (ref "CN1") (pin "P$89") (pinfunction "SIZ1_P89_P$89") (pintype "bidirectional"))
      (node (ref "RAMCPLD") (pin "39") (pinfunction "PB03/10_39") (pintype "bidirectional"))
    )
    (net (code "114") (name "TCK") (class "Default")
      (node (ref "JTAG") (pin "4") (pinfunction "4_4") (pintype "passive"))
      (node (ref "MUXCPLD") (pin "11") (pinfunction "TCK_11") (pintype "input"))
      (node (ref "RAMCPLD") (pin "30") (pinfunction "TCK_30") (pintype "bidirectional"))
    )
    (net (code "115") (name "TDI") (class "Default")
      (node (ref "JTAG") (pin "2") (pinfunction "2_2") (pintype "passive"))
      (node (ref "RAMCPLD") (pin "28") (pinfunction "TDI_28") (pintype "bidirectional"))
    )
    (net (code "116") (name "TDINT") (class "Default")
      (node (ref "MUXCPLD") (pin "9") (pinfunction "TDI_9") (pintype "input"))
      (node (ref "RAMCPLD") (pin "53") (pinfunction "TDO_53") (pintype "bidirectional"))
    )
    (net (code "117") (name "TDO") (class "Default")
      (node (ref "JTAG") (pin "3") (pinfunction "3_3") (pintype "passive"))
      (node (ref "MUXCPLD") (pin "24") (pinfunction "TDO_24") (pintype "output"))
    )
    (net (code "118") (name "TMS") (class "Default")
      (node (ref "JTAG") (pin "1") (pinfunction "1_1") (pintype "passive"))
      (node (ref "MUXCPLD") (pin "10") (pinfunction "TMS_10") (pintype "input"))
      (node (ref "RAMCPLD") (pin "29") (pinfunction "TMS_29") (pintype "bidirectional"))
    )
    (net (code "119") (name "VCC") (class "Default")
      (node (ref "C2") (pin "2") (pinfunction "P$2_2") (pintype "passive"))
      (node (ref "CN1") (pin "P$10") (pinfunction "VCC_P10_P$10") (pintype "bidirectional"))
      (node (ref "CN1") (pin "P$102") (pinfunction "VCC_P102_P$102") (pintype "bidirectional"))
      (node (ref "CN1") (pin "P$120") (pinfunction "VCC_P120_P$120") (pintype "bidirectional"))
      (node (ref "CN1") (pin "P$20") (pinfunction "VCC_P20_P$20") (pintype "bidirectional"))
      (node (ref "CN1") (pin "P$30") (pinfunction "VCC_P30_P$30") (pintype "bidirectional"))
      (node (ref "CN1") (pin "P$40") (pinfunction "VCC_P40_P$40") (pintype "bidirectional"))
      (node (ref "CN1") (pin "P$50") (pinfunction "VCC_P50_P$50") (pintype "bidirectional"))
      (node (ref "CN1") (pin "P$60") (pinfunction "VCC_P60_P$60") (pintype "bidirectional"))
      (node (ref "CN1") (pin "P$70") (pinfunction "VCC_P70_P$70") (pintype "bidirectional"))
      (node (ref "CN1") (pin "P$80") (pinfunction "VCC_P80_P$80") (pintype "bidirectional"))
      (node (ref "IC6") (pin "1") (pinfunction "VI_1") (pintype "bidirectional"))
    )
    (net (code "120") (name "VCC33") (class "Default")
      (node (ref "C1") (pin "2") (pinfunction "2_2") (pintype "passive"))
      (node (ref "C3") (pin "1") (pinfunction "P$1_1") (pintype "passive"))
      (node (ref "C5") (pin "1") (pinfunction "1_1") (pintype "passive"))
      (node (ref "IC1") (pin "1") (pinfunction "VDD_1") (pintype "bidirectional"))
      (node (ref "IC1") (pin "22") (pinfunction "VDD-1_22") (pintype "bidirectional"))
      (node (ref "IC1") (pin "6") (pinfunction "VDD-0_6") (pintype "bidirectional"))
      (node (ref "IC2") (pin "1") (pinfunction "VDD_1") (pintype "bidirectional"))
      (node (ref "IC2") (pin "22") (pinfunction "VDD-1_22") (pintype "bidirectional"))
      (node (ref "IC2") (pin "6") (pinfunction "VDD-0_6") (pintype "bidirectional"))
      (node (ref "IC3") (pin "1") (pinfunction "VDD_1") (pintype "bidirectional"))
      (node (ref "IC3") (pin "22") (pinfunction "VDD-1_22") (pintype "bidirectional"))
      (node (ref "IC3") (pin "6") (pinfunction "VDD-0_6") (pintype "bidirectional"))
      (node (ref "IC4") (pin "1") (pinfunction "VDD_1") (pintype "bidirectional"))
      (node (ref "IC4") (pin "22") (pinfunction "VDD-1_22") (pintype "bidirectional"))
      (node (ref "IC4") (pin "6") (pinfunction "VDD-0_6") (pintype "bidirectional"))
      (node (ref "IC6") (pin "2") (pinfunction "VO_2") (pintype "bidirectional"))
      (node (ref "ICC1") (pin "2") (pinfunction "P$2_2") (pintype "passive"))
      (node (ref "ICC2") (pin "2") (pinfunction "P$2_2") (pintype "passive"))
      (node (ref "ICC3") (pin "2") (pinfunction "P$2_2") (pintype "passive"))
      (node (ref "ICC4") (pin "2") (pinfunction "P$2_2") (pintype "passive"))
      (node (ref "JTAG") (pin "6") (pinfunction "6_6") (pintype "passive"))
      (node (ref "MUXCPLD") (pin "15") (pinfunction "VCCINT_15") (pintype "power_in"))
      (node (ref "MUXCPLD") (pin "26") (pinfunction "VCCIO_26") (pintype "power_in"))
      (node (ref "MUXCPLD") (pin "35") (pinfunction "VCCINT/VPP_35") (pintype "input"))
      (node (ref "RAMCPLD") (pin "26") (pinfunction "VCCIO_26") (pintype "bidirectional"))
      (node (ref "RAMCPLD") (pin "3") (pinfunction "VCCINT_3") (pintype "bidirectional"))
      (node (ref "RAMCPLD") (pin "37") (pinfunction "VCCINT/VPP_37") (pintype "bidirectional"))
      (node (ref "RAMCPLD") (pin "55") (pinfunction "VCCIO_55") (pintype "bidirectional"))
    )
    (net (code "121") (name "_FPUCS") (class "Default")
      (node (ref "CN1") (pin "P$115") (pinfunction "~{FPU_CS}_P115_P$115") (pintype "bidirectional"))
    )
    (net (code "122") (name "unconnected-(CN1--12V_P150-PadP$150)") (class "Default")
      (node (ref "CN1") (pin "P$150") (pinfunction "-12V_P150_P$150") (pintype "bidirectional"))
    )
    (net (code "123") (name "unconnected-(CN1-12V_P149-PadP$149)") (class "Default")
      (node (ref "CN1") (pin "P$149") (pinfunction "12V_P149_P$149") (pintype "bidirectional"))
    )
    (net (code "124") (name "unconnected-(CN1-AGND_P146-PadP$146)") (class "Default")
      (node (ref "CN1") (pin "P$146") (pinfunction "AGND_P146_P$146") (pintype "bidirectional"))
    )
    (net (code "125") (name "unconnected-(CN1-CCK_P117-PadP$117)") (class "Default")
      (node (ref "CN1") (pin "P$117") (pinfunction "CCK_P117_P$117") (pintype "bidirectional"))
    )
    (net (code "126") (name "unconnected-(CN1-E_P100-PadP$100)") (class "Default")
      (node (ref "CN1") (pin "P$100") (pinfunction "E_P100_P$100") (pintype "bidirectional"))
    )
    (net (code "127") (name "unconnected-(CN1-GND_P119-PadP$119)") (class "Default")
      (node (ref "CN1") (pin "P$119") (pinfunction "GND_P119_P$119") (pintype "bidirectional"))
    )
    (net (code "128") (name "unconnected-(CN1-GND_P139-PadP$139)") (class "Default")
      (node (ref "CN1") (pin "P$139") (pinfunction "GND_P139_P$139") (pintype "bidirectional"))
    )
    (net (code "129") (name "unconnected-(CN1-LEFT_P147-PadP$147)") (class "Default")
      (node (ref "CN1") (pin "P$147") (pinfunction "LEFT_P147_P$147") (pintype "bidirectional"))
    )
    (net (code "130") (name "unconnected-(CN1-RIGHT_P148-PadP$148)") (class "Default")
      (node (ref "CN1") (pin "P$148") (pinfunction "RIGHT_P148_P$148") (pintype "bidirectional"))
    )
    (net (code "131") (name "unconnected-(CN1-SYSTEM0_P142-PadP$142)") (class "Default")
      (node (ref "CN1") (pin "P$142") (pinfunction "SYSTEM0_P142_P$142") (pintype "bidirectional"))
    )
    (net (code "132") (name "unconnected-(CN1-SYSTEM1_P141-PadP$141)") (class "Default")
      (node (ref "CN1") (pin "P$141") (pinfunction "SYSTEM1_P141_P$141") (pintype "bidirectional"))
    )
    (net (code "133") (name "unconnected-(CN1-VCC_P140-PadP$140)") (class "Default")
      (node (ref "CN1") (pin "P$140") (pinfunction "VCC_P140_P$140") (pintype "bidirectional"))
    )
    (net (code "134") (name "unconnected-(CN1-XRDY_P134-PadP$134)") (class "Default")
      (node (ref "CN1") (pin "P$134") (pinfunction "XRDY_P134_P$134") (pintype "bidirectional"))
    )
    (net (code "135") (name "unconnected-(CN1-~{BGACK}(NC)_P113-PadP$113)") (class "Default")
      (node (ref "CN1") (pin "P$113") (pinfunction "~{BGACK}(NC)_P113_P$113") (pintype "bidirectional"))
    )
    (net (code "136") (name "unconnected-(CN1-~{BG}_P112-PadP$112)") (class "Default")
      (node (ref "CN1") (pin "P$112") (pinfunction "~{BG}_P112_P$112") (pintype "bidirectional"))
    )
    (net (code "137") (name "unconnected-(CN1-~{BOSS}_P114-PadP$114)") (class "Default")
      (node (ref "CN1") (pin "P$114") (pinfunction "~{BOSS}_P114_P$114") (pintype "bidirectional"))
    )
    (net (code "138") (name "unconnected-(CN1-~{BR}_P111-PadP$111)") (class "Default")
      (node (ref "CN1") (pin "P$111") (pinfunction "~{BR}_P111_P$111") (pintype "bidirectional"))
    )
    (net (code "139") (name "unconnected-(CN1-~{CBACK}(NC)_P110-PadP$110)") (class "Default")
      (node (ref "CN1") (pin "P$110") (pinfunction "~{CBACK}(NC)_P110_P$110") (pintype "bidirectional"))
    )
    (net (code "140") (name "unconnected-(CN1-~{CBREQ}(NC)_109-PadP$109)") (class "Default")
      (node (ref "CN1") (pin "P$109") (pinfunction "~{CBREQ}(NC)_109_P$109") (pintype "bidirectional"))
    )
    (net (code "141") (name "unconnected-(CN1-~{CC_ENA}_P126-PadP$126)") (class "Default")
      (node (ref "CN1") (pin "P$126") (pinfunction "~{CC_ENA}_P126_P$126") (pintype "bidirectional"))
    )
    (net (code "142") (name "unconnected-(CN1-~{CIIN}(NC)_P107-PadP$107)") (class "Default")
      (node (ref "CN1") (pin "P$107") (pinfunction "~{CIIN}(NC)_P107_P$107") (pintype "bidirectional"))
    )
    (net (code "143") (name "unconnected-(CN1-~{CIOUT}(NC)_P108-PadP$108)") (class "Default")
      (node (ref "CN1") (pin "P$108") (pinfunction "~{CIOUT}(NC)_P108_P$108") (pintype "bidirectional"))
    )
    (net (code "144") (name "unconnected-(CN1-~{ECS}(NC)_P87-PadP$87)") (class "Default")
      (node (ref "CN1") (pin "P$87") (pinfunction "~{ECS}(NC)_P87_P$87") (pintype "bidirectional"))
    )
    (net (code "145") (name "unconnected-(CN1-~{FLASH}_P124-PadP$124)") (class "Default")
      (node (ref "CN1") (pin "P$124") (pinfunction "~{FLASH}_P124_P$124") (pintype "bidirectional"))
    )
    (net (code "146") (name "unconnected-(CN1-~{HLT}_P86-PadP$86)") (class "Default")
      (node (ref "CN1") (pin "P$86") (pinfunction "~{HLT}_P86_P$86") (pintype "bidirectional"))
    )
    (net (code "147") (name "unconnected-(CN1-~{IORDY}_P129-PadP$129)") (class "Default")
      (node (ref "CN1") (pin "P$129") (pinfunction "~{IORDY}_P129_P$129") (pintype "bidirectional"))
    )
    (net (code "148") (name "unconnected-(CN1-~{IOWR}_P130-PadP$130)") (class "Default")
      (node (ref "CN1") (pin "P$130") (pinfunction "~{IOWR}_P130_P$130") (pintype "bidirectional"))
    )
    (net (code "149") (name "unconnected-(CN1-~{IPEND}(NC)_P84-PadP$84)") (class "Default")
      (node (ref "CN1") (pin "P$84") (pinfunction "~{IPEND}(NC)_P84_P$84") (pintype "bidirectional"))
    )
    (net (code "150") (name "unconnected-(CN1-~{KB_RESET}_P128-PadP$128)") (class "Default")
      (node (ref "CN1") (pin "P$128") (pinfunction "~{KB_RESET}_P128_P$128") (pintype "bidirectional"))
    )
    (net (code "151") (name "unconnected-(CN1-~{NET_CS}_P121-PadP$121)") (class "Default")
      (node (ref "CN1") (pin "P$121") (pinfunction "~{NET_CS}_P121_P$121") (pintype "bidirectional"))
    )
    (net (code "152") (name "unconnected-(CN1-~{OCS}(NC)_P88-PadP$88)") (class "Default")
      (node (ref "CN1") (pin "P$88") (pinfunction "~{OCS}(NC)_P88_P$88") (pintype "bidirectional"))
    )
    (net (code "153") (name "unconnected-(CN1-~{OE}_P131-PadP$131)") (class "Default")
      (node (ref "CN1") (pin "P$131") (pinfunction "~{OE}_P131_P$131") (pintype "bidirectional"))
    )
    (net (code "154") (name "unconnected-(CN1-~{REG}_P125-PadP$125)") (class "Default")
      (node (ref "CN1") (pin "P$125") (pinfunction "~{REG}_P125_P$125") (pintype "bidirectional"))
    )
    (net (code "155") (name "unconnected-(CN1-~{RMC}_P106-PadP$106)") (class "Default")
      (node (ref "CN1") (pin "P$106") (pinfunction "~{RMC}_P106_P$106") (pintype "bidirectional"))
    )
    (net (code "156") (name "unconnected-(CN1-~{RTC_CS}_P123-PadP$123)") (class "Default")
      (node (ref "CN1") (pin "P$123") (pinfunction "~{RTC_CS}_P123_P$123") (pintype "bidirectional"))
    )
    (net (code "157") (name "unconnected-(CN1-~{SPARE_CS}_P122-PadP$122)") (class "Default")
      (node (ref "CN1") (pin "P$122") (pinfunction "~{SPARE_CS}_P122_P$122") (pintype "bidirectional"))
    )
    (net (code "158") (name "unconnected-(CN1-~{STERM}(NC)_P95-PadP$95)") (class "Default")
      (node (ref "CN1") (pin "P$95") (pinfunction "~{STERM}(NC)_P95_P$95") (pintype "bidirectional"))
    )
    (net (code "159") (name "unconnected-(CN1-~{WAIT}_P127-PadP$127)") (class "Default")
      (node (ref "CN1") (pin "P$127") (pinfunction "~{WAIT}_P127_P$127") (pintype "bidirectional"))
    )
    (net (code "160") (name "unconnected-(CN1-~{WE}_P132-PadP$132)") (class "Default")
      (node (ref "CN1") (pin "P$132") (pinfunction "~{WE}_P132_P$132") (pintype "bidirectional"))
    )
    (net (code "161") (name "unconnected-(CN1-~{WIDE}_P136-PadP$136)") (class "Default")
      (node (ref "CN1") (pin "P$136") (pinfunction "~{WIDE}_P136_P$136") (pintype "bidirectional"))
    )
    (net (code "162") (name "unconnected-(CN1-~{XRXD}_P143-PadP$143)") (class "Default")
      (node (ref "CN1") (pin "P$143") (pinfunction "~{XRXD}_P143_P$143") (pintype "bidirectional"))
    )
    (net (code "163") (name "unconnected-(CN1-~{XTXD}_P144-PadP$144)") (class "Default")
      (node (ref "CN1") (pin "P$144") (pinfunction "~{XTXD}_P144_P$144") (pintype "bidirectional"))
    )
    (net (code "164") (name "unconnected-(CN1-~{ZORRO}_P135-PadP$135)") (class "Default")
      (node (ref "CN1") (pin "P$135") (pinfunction "~{ZORRO}_P135_P$135") (pintype "bidirectional"))
    )
    (net (code "165") (name "unconnected-(IC1-NC-0-Pad12)") (class "Default")
      (node (ref "IC1") (pin "12") (pinfunction "NC-0_12") (pintype "bidirectional"))
    )
    (net (code "166") (name "unconnected-(IC1-NC-1-Pad13)") (class "Default")
      (node (ref "IC1") (pin "13") (pinfunction "NC-1_13") (pintype "bidirectional"))
    )
    (net (code "167") (name "unconnected-(IC1-NC-2-Pad16)") (class "Default")
      (node (ref "IC1") (pin "16") (pinfunction "NC-2_16") (pintype "bidirectional"))
    )
    (net (code "168") (name "unconnected-(IC1-NC-3-Pad17)") (class "Default")
      (node (ref "IC1") (pin "17") (pinfunction "NC-3_17") (pintype "bidirectional"))
    )
    (net (code "169") (name "unconnected-(IC1-NC-4-Pad33)") (class "Default")
      (node (ref "IC1") (pin "33") (pinfunction "NC-4_33") (pintype "bidirectional"))
    )
    (net (code "170") (name "unconnected-(IC1-NC-5-Pad34)") (class "Default")
      (node (ref "IC1") (pin "34") (pinfunction "NC-5_34") (pintype "bidirectional"))
    )
    (net (code "171") (name "unconnected-(IC1-NC-Pad11)") (class "Default")
      (node (ref "IC1") (pin "11") (pinfunction "NC_11") (pintype "bidirectional"))
    )
    (net (code "172") (name "unconnected-(IC2-NC-0-Pad12)") (class "Default")
      (node (ref "IC2") (pin "12") (pinfunction "NC-0_12") (pintype "bidirectional"))
    )
    (net (code "173") (name "unconnected-(IC2-NC-1-Pad13)") (class "Default")
      (node (ref "IC2") (pin "13") (pinfunction "NC-1_13") (pintype "bidirectional"))
    )
    (net (code "174") (name "unconnected-(IC2-NC-2-Pad16)") (class "Default")
      (node (ref "IC2") (pin "16") (pinfunction "NC-2_16") (pintype "bidirectional"))
    )
    (net (code "175") (name "unconnected-(IC2-NC-3-Pad17)") (class "Default")
      (node (ref "IC2") (pin "17") (pinfunction "NC-3_17") (pintype "bidirectional"))
    )
    (net (code "176") (name "unconnected-(IC2-NC-4-Pad33)") (class "Default")
      (node (ref "IC2") (pin "33") (pinfunction "NC-4_33") (pintype "bidirectional"))
    )
    (net (code "177") (name "unconnected-(IC2-NC-5-Pad34)") (class "Default")
      (node (ref "IC2") (pin "34") (pinfunction "NC-5_34") (pintype "bidirectional"))
    )
    (net (code "178") (name "unconnected-(IC2-NC-Pad11)") (class "Default")
      (node (ref "IC2") (pin "11") (pinfunction "NC_11") (pintype "bidirectional"))
    )
    (net (code "179") (name "unconnected-(IC3-NC-0-Pad12)") (class "Default")
      (node (ref "IC3") (pin "12") (pinfunction "NC-0_12") (pintype "bidirectional"))
    )
    (net (code "180") (name "unconnected-(IC3-NC-1-Pad13)") (class "Default")
      (node (ref "IC3") (pin "13") (pinfunction "NC-1_13") (pintype "bidirectional"))
    )
    (net (code "181") (name "unconnected-(IC3-NC-2-Pad16)") (class "Default")
      (node (ref "IC3") (pin "16") (pinfunction "NC-2_16") (pintype "bidirectional"))
    )
    (net (code "182") (name "unconnected-(IC3-NC-3-Pad17)") (class "Default")
      (node (ref "IC3") (pin "17") (pinfunction "NC-3_17") (pintype "bidirectional"))
    )
    (net (code "183") (name "unconnected-(IC3-NC-4-Pad33)") (class "Default")
      (node (ref "IC3") (pin "33") (pinfunction "NC-4_33") (pintype "bidirectional"))
    )
    (net (code "184") (name "unconnected-(IC3-NC-5-Pad34)") (class "Default")
      (node (ref "IC3") (pin "34") (pinfunction "NC-5_34") (pintype "bidirectional"))
    )
    (net (code "185") (name "unconnected-(IC3-NC-Pad11)") (class "Default")
      (node (ref "IC3") (pin "11") (pinfunction "NC_11") (pintype "bidirectional"))
    )
    (net (code "186") (name "unconnected-(IC4-NC-0-Pad12)") (class "Default")
      (node (ref "IC4") (pin "12") (pinfunction "NC-0_12") (pintype "bidirectional"))
    )
    (net (code "187") (name "unconnected-(IC4-NC-1-Pad13)") (class "Default")
      (node (ref "IC4") (pin "13") (pinfunction "NC-1_13") (pintype "bidirectional"))
    )
    (net (code "188") (name "unconnected-(IC4-NC-2-Pad16)") (class "Default")
      (node (ref "IC4") (pin "16") (pinfunction "NC-2_16") (pintype "bidirectional"))
    )
    (net (code "189") (name "unconnected-(IC4-NC-3-Pad17)") (class "Default")
      (node (ref "IC4") (pin "17") (pinfunction "NC-3_17") (pintype "bidirectional"))
    )
    (net (code "190") (name "unconnected-(IC4-NC-4-Pad33)") (class "Default")
      (node (ref "IC4") (pin "33") (pinfunction "NC-4_33") (pintype "bidirectional"))
    )
    (net (code "191") (name "unconnected-(IC4-NC-5-Pad34)") (class "Default")
      (node (ref "IC4") (pin "34") (pinfunction "NC-5_34") (pintype "bidirectional"))
    )
    (net (code "192") (name "unconnected-(IC4-NC-Pad11)") (class "Default")
      (node (ref "IC4") (pin "11") (pinfunction "NC_11") (pintype "bidirectional"))
    )
    (net (code "193") (name "unconnected-(MUXCPLD-PB00{slash}00-Pad40)") (class "Default")
      (node (ref "MUXCPLD") (pin "40") (pinfunction "PB00/00_40") (pintype "bidirectional"))
    )
    (net (code "194") (name "unconnected-(MUXCPLD-PB00{slash}01-Pad41)") (class "Default")
      (node (ref "MUXCPLD") (pin "41") (pinfunction "PB00/01_41") (pintype "bidirectional"))
    )
    (net (code "195") (name "unconnected-(MUXCPLD-PB00{slash}03-Pad42)") (class "Default")
      (node (ref "MUXCPLD") (pin "42") (pinfunction "PB00/03_42") (pintype "bidirectional"))
    )
  )
)
